# Wideband.net
KiCad netlist of a schematic drawn in Altium Designer
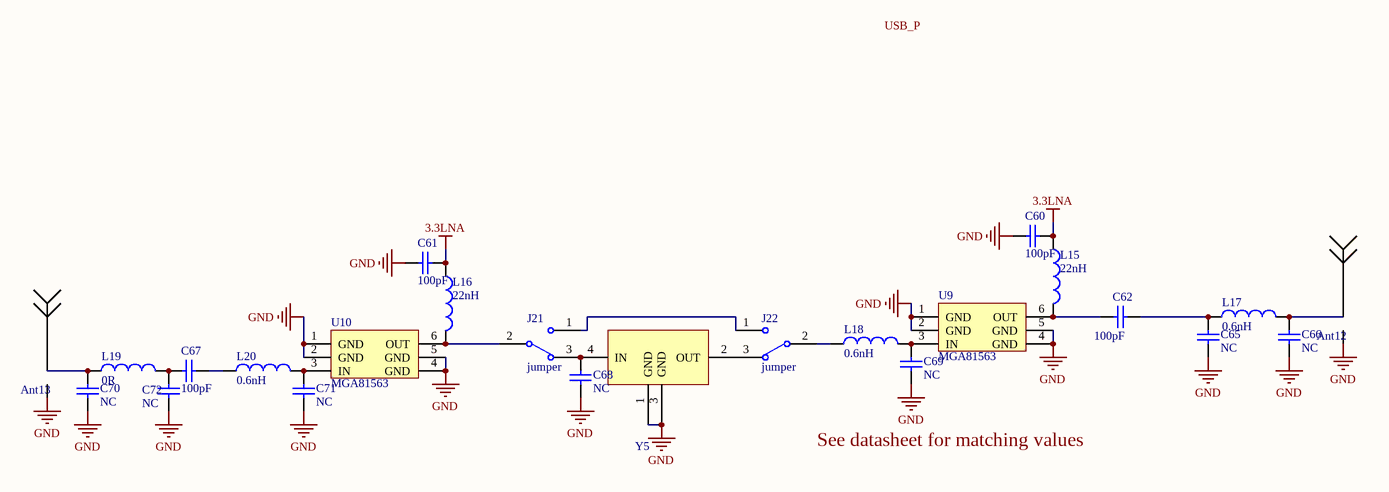
[diagram p0: Wideband.SchDoc]

(export (version "E")
  (design (tool "Eeschema 10.0.6"))
  (components
    (comp (ref "Ant12") (value "Antenna") (footprint "SMA-2") (libsource (lib "F4SDR") (part "Antenna")))
    (comp (ref "Ant13") (value "Antenna") (footprint "SMA-2") (libsource (lib "F4SDR") (part "Antenna")))
    (comp (ref "C60")
      (value "100pF")
      (footprint "0402")
      (description "Capacitor")
      (fields (field (name "Comment") "Cap") (field (name "PUBLISHER") "Altium Limited"))
      (libsource (lib "RTC6705") (part "Cap"))
    )
    (comp (ref "C61")
      (value "100pF")
      (footprint "0402")
      (description "Capacitor")
      (fields (field (name "Comment") "Cap") (field (name "PUBLISHER") "Altium Limited"))
      (libsource (lib "RTC6705") (part "Cap"))
    )
    (comp (ref "C62")
      (value "100pF")
      (footprint "0402")
      (description "Capacitor")
      (fields (field (name "Comment") "Cap") (field (name "PUBLISHER") "Altium Limited"))
      (libsource (lib "RTC6705") (part "Cap"))
    )
    (comp (ref "C65")
      (value "NC")
      (footprint "0402")
      (description "Capacitor")
      (fields (field (name "Comment") "Cap") (field (name "PUBLISHER") "Altium Limited"))
      (libsource (lib "RTC6705") (part "Cap"))
    )
    (comp (ref "C66")
      (value "NC")
      (footprint "0402")
      (description "Capacitor")
      (fields (field (name "Comment") "Cap") (field (name "PUBLISHER") "Altium Limited"))
      (libsource (lib "RTC6705") (part "Cap"))
    )
    (comp (ref "C67")
      (value "100pF")
      (footprint "0402")
      (description "Capacitor")
      (fields (field (name "Comment") "Cap") (field (name "PUBLISHER") "Altium Limited"))
      (libsource (lib "RTC6705") (part "Cap"))
    )
    (comp (ref "C68")
      (value "NC")
      (footprint "0402")
      (description "Capacitor")
      (fields (field (name "Comment") "Cap") (field (name "PUBLISHER") "Altium Limited"))
      (libsource (lib "RTC6705") (part "Cap"))
    )
    (comp (ref "C69")
      (value "NC")
      (footprint "0402")
      (description "Capacitor")
      (fields (field (name "Comment") "Cap") (field (name "PUBLISHER") "Altium Limited"))
      (libsource (lib "RTC6705") (part "Cap"))
    )
    (comp (ref "C70")
      (value "NC")
      (footprint "0402")
      (description "Capacitor")
      (fields (field (name "Comment") "Cap") (field (name "PUBLISHER") "Altium Limited"))
      (libsource (lib "RTC6705") (part "Cap"))
    )
    (comp (ref "C71")
      (value "NC")
      (footprint "0402")
      (description "Capacitor")
      (fields (field (name "Comment") "Cap") (field (name "PUBLISHER") "Altium Limited"))
      (libsource (lib "RTC6705") (part "Cap"))
    )
    (comp (ref "C72")
      (value "NC")
      (footprint "0402")
      (description "Capacitor")
      (fields (field (name "Comment") "Cap") (field (name "PUBLISHER") "Altium Limited"))
      (libsource (lib "RTC6705") (part "Cap"))
    )
    (comp (ref "J21")
      (value "jumper")
      (footprint "0402J")
      (description "SPDT Subminiature Toggle Switch, Right Angle Mounting, Vertical Actuation")
      (fields (field (name "PUBLISHER") "Altium Limited"))
      (libsource (lib "Miscellaneous Devices") (part "SW-SPDT"))
    )
    (comp (ref "J22")
      (value "jumper")
      (footprint "0402J")
      (description "SPDT Subminiature Toggle Switch, Right Angle Mounting, Vertical Actuation")
      (fields (field (name "PUBLISHER") "Altium Limited"))
      (libsource (lib "Miscellaneous Devices") (part "SW-SPDT"))
    )
    (comp (ref "L15")
      (value "22nH")
      (footprint "0603")
      (description "Inductor")
      (fields (field (name "PUBLISHER") "Altium Limited"))
      (libsource (lib "Miscellaneous Devices") (part "Inductor"))
    )
    (comp (ref "L16")
      (value "22nH")
      (footprint "0603")
      (description "Inductor")
      (fields (field (name "PUBLISHER") "Altium Limited"))
      (libsource (lib "Miscellaneous Devices") (part "Inductor"))
    )
    (comp (ref "L17")
      (value "0.6nH")
      (footprint "0402")
      (description "Inductor")
      (fields (field (name "PUBLISHER") "Altium Limited"))
      (libsource (lib "Miscellaneous Devices") (part "Inductor"))
    )
    (comp (ref "L18")
      (value "0.6nH")
      (footprint "0402")
      (description "Inductor")
      (fields (field (name "PUBLISHER") "Altium Limited"))
      (libsource (lib "Miscellaneous Devices") (part "Inductor"))
    )
    (comp (ref "L19")
      (value "0R")
      (footprint "0402")
      (description "Inductor")
      (fields (field (name "PUBLISHER") "Altium Limited"))
      (libsource (lib "Miscellaneous Devices") (part "Inductor"))
    )
    (comp (ref "L20")
      (value "0.6nH")
      (footprint "0402")
      (description "Inductor")
      (fields (field (name "PUBLISHER") "Altium Limited"))
      (libsource (lib "Miscellaneous Devices") (part "Inductor"))
    )
    (comp (ref "U9") (value "MGA81563") (footprint "SC-70-6") (libsource (lib "F4SDR") (part "MGA81563")))
    (comp (ref "U10") (value "MGA81563") (footprint "SC-70-6") (libsource (lib "F4SDR") (part "MGA81563")))
    (comp (ref "Y5")
      (value "2450BP39C100A")
      (footprint "2450BP39C100A")
      (libsource (lib "F4SDR") (part "2450BP39C100A"))
    )
  )
  (nets
    (net (code "2") (name "3.3LNA") (class "Default")
      (node (ref "C60") (pin "2") (pinfunction "2_2") (pintype "passive"))
      (node (ref "C61") (pin "2") (pinfunction "2_2") (pintype "passive"))
      (node (ref "L15") (pin "1") (pinfunction "1_1") (pintype "passive"))
      (node (ref "L16") (pin "1") (pinfunction "1_1") (pintype "passive"))
    )
    (net (code "3") (name "GND") (class "Default")
      (node (ref "Ant12") (pin "GND") (pinfunction "G_GND") (pintype "passive"))
      (node (ref "Ant13") (pin "GND") (pinfunction "G_GND") (pintype "passive"))
      (node (ref "C60") (pin "1") (pinfunction "1_1") (pintype "passive"))
      (node (ref "C61") (pin "1") (pinfunction "1_1") (pintype "passive"))
      (node (ref "C65") (pin "1") (pinfunction "1_1") (pintype "passive"))
      (node (ref "C66") (pin "1") (pinfunction "1_1") (pintype "passive"))
      (node (ref "C68") (pin "1") (pinfunction "1_1") (pintype "passive"))
      (node (ref "C69") (pin "1") (pinfunction "1_1") (pintype "passive"))
      (node (ref "C70") (pin "1") (pinfunction "1_1") (pintype "passive"))
      (node (ref "C71") (pin "1") (pinfunction "1_1") (pintype "passive"))
      (node (ref "C72") (pin "1") (pinfunction "1_1") (pintype "passive"))
      (node (ref "U10") (pin "1") (pinfunction "GND_1") (pintype "passive"))
      (node (ref "U10") (pin "2") (pinfunction "GND_2") (pintype "passive"))
      (node (ref "U10") (pin "4") (pinfunction "GND_4") (pintype "passive"))
      (node (ref "U10") (pin "5") (pinfunction "GND_5") (pintype "passive"))
      (node (ref "U9") (pin "1") (pinfunction "GND_1") (pintype "passive"))
      (node (ref "U9") (pin "2") (pinfunction "GND_2") (pintype "passive"))
      (node (ref "U9") (pin "4") (pinfunction "GND_4") (pintype "passive"))
      (node (ref "U9") (pin "5") (pinfunction "GND_5") (pintype "passive"))
      (node (ref "Y5") (pin "1") (pinfunction "GND_1") (pintype "passive"))
      (node (ref "Y5") (pin "3") (pinfunction "GND_3") (pintype "passive"))
    )
    (net (code "4") (name "Net-(Ant12-Pad1)") (class "Default")
      (node (ref "Ant12") (pin "1") (pinfunction "1_1") (pintype "passive"))
      (node (ref "C66") (pin "2") (pinfunction "2_2") (pintype "passive"))
      (node (ref "L17") (pin "2") (pinfunction "2_2") (pintype "passive"))
    )
    (net (code "5") (name "Net-(Ant13-Pad1)") (class "Default")
      (node (ref "Ant13") (pin "1") (pinfunction "1_1") (pintype "passive"))
      (node (ref "C70") (pin "2") (pinfunction "2_2") (pintype "passive"))
      (node (ref "L19") (pin "1") (pinfunction "1_1") (pintype "passive"))
    )
    (net (code "6") (name "Net-(C62-Pad2)") (class "Default")
      (node (ref "C62") (pin "2") (pinfunction "2_2") (pintype "passive"))
      (node (ref "C65") (pin "2") (pinfunction "2_2") (pintype "passive"))
      (node (ref "L17") (pin "1") (pinfunction "1_1") (pintype "passive"))
    )
    (net (code "7") (name "Net-(C67-Pad1)") (class "Default")
      (node (ref "C67") (pin "1") (pinfunction "1_1") (pintype "passive"))
      (node (ref "C72") (pin "2") (pinfunction "2_2") (pintype "passive"))
      (node (ref "L19") (pin "2") (pinfunction "2_2") (pintype "passive"))
    )
    (net (code "8") (name "Net-(C67-Pad2)") (class "Default")
      (node (ref "C67") (pin "2") (pinfunction "2_2") (pintype "passive"))
      (node (ref "L20") (pin "1") (pinfunction "1_1") (pintype "passive"))
    )
    (net (code "9") (name "Net-(J21-Pad1)") (class "Default")
      (node (ref "J21") (pin "1") (pinfunction "1_1") (pintype "passive"))
      (node (ref "J22") (pin "1") (pinfunction "1_1") (pintype "passive"))
    )
    (net (code "10") (name "Net-(J22-Pad2)") (class "Default")
      (node (ref "J22") (pin "2") (pinfunction "2_2") (pintype "passive"))
      (node (ref "L18") (pin "1") (pinfunction "1_1") (pintype "passive"))
    )
    (net (code "11") (name "Net-(U9-IN)") (class "Default")
      (node (ref "C69") (pin "2") (pinfunction "2_2") (pintype "passive"))
      (node (ref "L18") (pin "2") (pinfunction "2_2") (pintype "passive"))
      (node (ref "U9") (pin "3") (pinfunction "IN_3") (pintype "passive"))
    )
    (net (code "12") (name "Net-(U9-OUT)") (class "Default")
      (node (ref "C62") (pin "1") (pinfunction "1_1") (pintype "passive"))
      (node (ref "L15") (pin "2") (pinfunction "2_2") (pintype "passive"))
      (node (ref "U9") (pin "6") (pinfunction "OUT_6") (pintype "passive"))
    )
    (net (code "13") (name "Net-(U10-IN)") (class "Default")
      (node (ref "C71") (pin "2") (pinfunction "2_2") (pintype "passive"))
      (node (ref "L20") (pin "2") (pinfunction "2_2") (pintype "passive"))
      (node (ref "U10") (pin "3") (pinfunction "IN_3") (pintype "passive"))
    )
    (net (code "14") (name "Net-(U10-OUT)") (class "Default")
      (node (ref "J21") (pin "2") (pinfunction "2_2") (pintype "passive"))
      (node (ref "L16") (pin "2") (pinfunction "2_2") (pintype "passive"))
      (node (ref "U10") (pin "6") (pinfunction "OUT_6") (pintype "passive"))
    )
    (net (code "15") (name "Net-(Y5-IN)") (class "Default")
      (node (ref "C68") (pin "2") (pinfunction "2_2") (pintype "passive"))
      (node (ref "J21") (pin "3") (pinfunction "3_3") (pintype "passive"))
      (node (ref "Y5") (pin "4") (pinfunction "IN_4") (pintype "passive"))
    )
    (net (code "16") (name "Net-(Y5-OUT)") (class "Default")
      (node (ref "J22") (pin "3") (pinfunction "3_3") (pintype "passive"))
      (node (ref "Y5") (pin "2") (pinfunction "OUT_2") (pintype "passive"))
    )
  )
)
